# decoder.net
KiCad netlist of a schematic drawn in Altium Designer
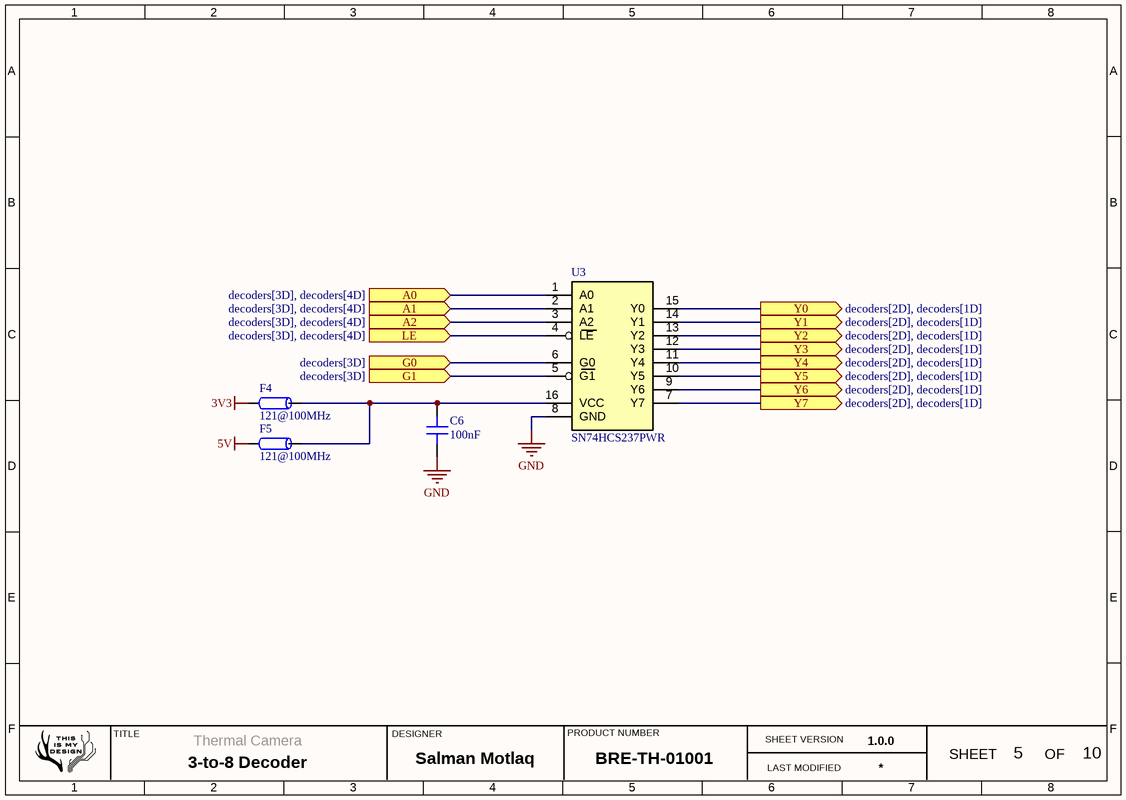
[diagram p0: decoder.SchDoc]

(export (version "E")
  (design (tool "Eeschema 10.0.6"))
  (components
    (comp (ref "C6")
      (value "100nF")
      (footprint "CAP 0603_1608")
      (description "SMT Capacitor")
      (libsource (lib "Capacitor") (part "Cap 0603"))
    )
    (comp (ref "F4")
      (value "121@100MHz")
      (footprint "Ferrite-0805")
      (description "Ferrite Bead")
      (libsource (lib "Salman_lib") (part "Ferrite Bead"))
    )
    (comp (ref "F5")
      (value "121@100MHz")
      (footprint "Ferrite-0805")
      (description "Ferrite Bead")
      (libsource (lib "Salman_lib") (part "Ferrite Bead"))
    )
    (comp (ref "U3")
      (value "SN74HCS237PWR")
      (footprint "TSSOP-16")
      (description "High speed CMOS logic 3-to-8 line decoder demultiplexer with address latches")
      (libsource (lib "Schem_lib") (part "SN74HCS237"))
    )
  )
  (nets
    (net (code "1") (name "/A0") (class "Default")
      (node (ref "U3") (pin "1") (pinfunction "A0_1") (pintype "passive"))
    )
    (net (code "2") (name "/A1") (class "Default")
      (node (ref "U3") (pin "2") (pinfunction "A1_2") (pintype "passive"))
    )
    (net (code "3") (name "/A2") (class "Default")
      (node (ref "U3") (pin "3") (pinfunction "A2_3") (pintype "passive"))
    )
    (net (code "4") (name "/G0") (class "Default")
      (node (ref "U3") (pin "6") (pinfunction "G0_6") (pintype "passive"))
    )
    (net (code "5") (name "/G1") (class "Default")
      (node (ref "U3") (pin "5") (pinfunction "G1_5") (pintype "passive"))
    )
    (net (code "6") (name "/LE") (class "Default")
      (node (ref "U3") (pin "4") (pinfunction "LE_4") (pintype "passive"))
    )
    (net (code "7") (name "/Y0") (class "Default")
      (node (ref "U3") (pin "15") (pinfunction "Y0_15") (pintype "passive"))
    )
    (net (code "8") (name "/Y1") (class "Default")
      (node (ref "U3") (pin "14") (pinfunction "Y1_14") (pintype "passive"))
    )
    (net (code "9") (name "/Y2") (class "Default")
      (node (ref "U3") (pin "13") (pinfunction "Y2_13") (pintype "passive"))
    )
    (net (code "10") (name "/Y3") (class "Default")
      (node (ref "U3") (pin "12") (pinfunction "Y3_12") (pintype "passive"))
    )
    (net (code "11") (name "/Y4") (class "Default")
      (node (ref "U3") (pin "11") (pinfunction "Y4_11") (pintype "passive"))
    )
    (net (code "12") (name "/Y5") (class "Default")
      (node (ref "U3") (pin "10") (pinfunction "Y5_10") (pintype "passive"))
    )
    (net (code "13") (name "/Y6") (class "Default")
      (node (ref "U3") (pin "9") (pinfunction "Y6_9") (pintype "passive"))
    )
    (net (code "14") (name "/Y7") (class "Default")
      (node (ref "U3") (pin "7") (pinfunction "Y7_7") (pintype "passive"))
    )
    (net (code "15") (name "3V3") (class "Default")
      (node (ref "F4") (pin "1") (pinfunction "67_1") (pintype "passive"))
    )
    (net (code "16") (name "5V") (class "Default")
      (node (ref "F5") (pin "1") (pinfunction "67_1") (pintype "passive"))
    )
    (net (code "17") (name "GND") (class "Default")
      (node (ref "C6") (pin "1") (pinfunction "1_1") (pintype "passive"))
      (node (ref "U3") (pin "8") (pinfunction "GND_8") (pintype "passive"))
    )
    (net (code "18") (name "Net-(F4-66)") (class "Default")
      (node (ref "C6") (pin "2") (pinfunction "2_2") (pintype "passive"))
      (node (ref "F4") (pin "2") (pinfunction "66_2") (pintype "passive"))
      (node (ref "F5") (pin "2") (pinfunction "66_2") (pintype "passive"))
      (node (ref "U3") (pin "16") (pinfunction "VCC_16") (pintype "passive"))
    )
  )
)
